# tvbgone.net
KiCad netlist of a schematic drawn in EAGLE
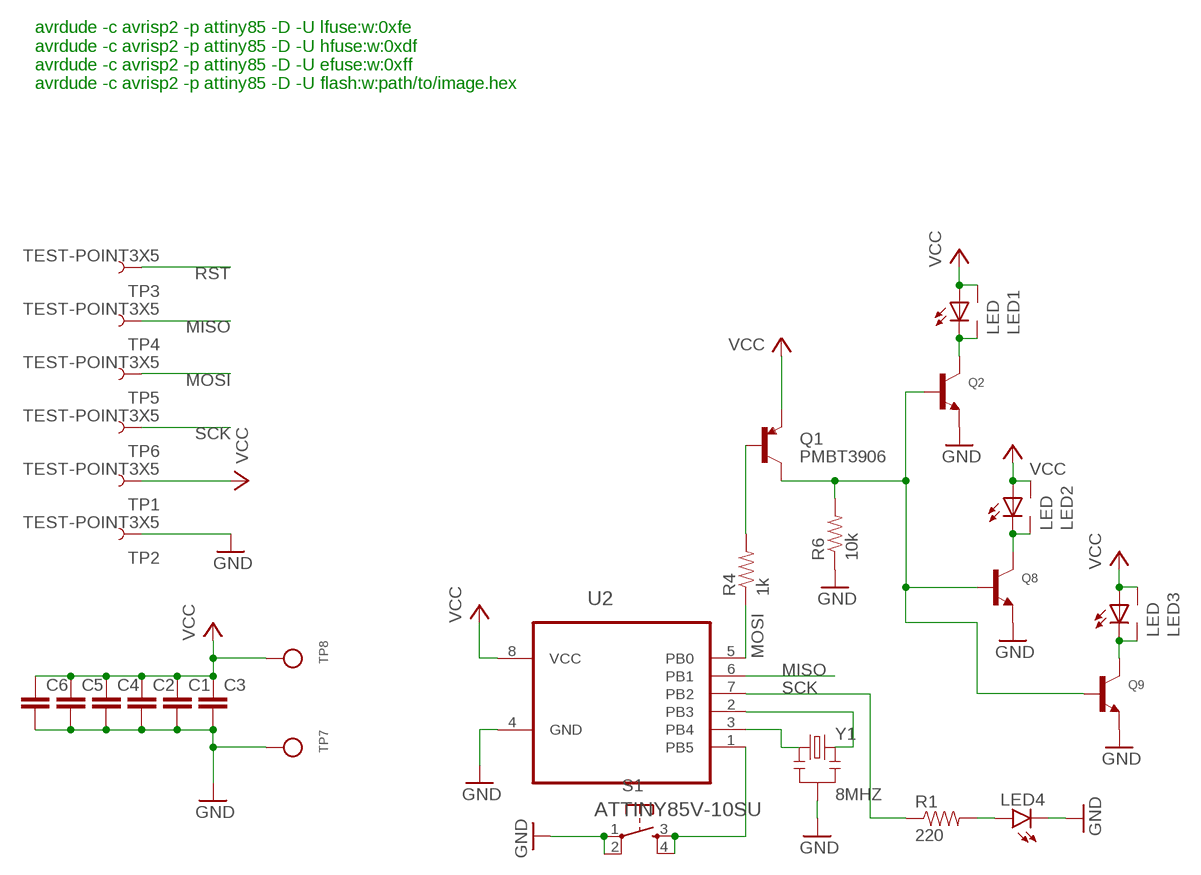
[diagram p0: schematic, sheet 1]

(export (version "E")
  (design (tool "Eeschema 10.0.6"))
  (components
    (comp (ref "C1")
      (value "CAP0603-CAP")
      (footprint "eagle-import:0603-CAP")
      (libsource (lib "eagle-import") (part "CAP0603-CAP"))
    )
    (comp (ref "C2")
      (value "CAP0603-CAP")
      (footprint "eagle-import:0603-CAP")
      (libsource (lib "eagle-import") (part "CAP0603-CAP"))
    )
    (comp (ref "C3")
      (value "CAP0603-CAP")
      (footprint "eagle-import:0603-CAP")
      (libsource (lib "eagle-import") (part "CAP0603-CAP"))
    )
    (comp (ref "C4")
      (value "CAP0603-CAP")
      (footprint "eagle-import:0603-CAP")
      (libsource (lib "eagle-import") (part "CAP0603-CAP"))
    )
    (comp (ref "C5")
      (value "CAP0603-CAP")
      (footprint "eagle-import:0603-CAP")
      (libsource (lib "eagle-import") (part "CAP0603-CAP"))
    )
    (comp (ref "C6")
      (value "CAP0603-CAP")
      (footprint "eagle-import:0603-CAP")
      (libsource (lib "eagle-import") (part "CAP0603-CAP"))
    )
    (comp (ref "LED1")
      (value "LED")
      (footprint "eagle-import:5MM-SIDE")
      (libsource (lib "eagle-import") (part "LED"))
    )
    (comp (ref "LED2")
      (value "LED")
      (footprint "eagle-import:5MM-SIDE")
      (libsource (lib "eagle-import") (part "LED"))
    )
    (comp (ref "LED3")
      (value "LED")
      (footprint "eagle-import:5MM-SIDE")
      (libsource (lib "eagle-import") (part "LED"))
    )
    (comp (ref "LED4")
      (value "LED0603")
      (footprint "eagle-import:LED-0603")
      (libsource (lib "eagle-import") (part "LED0603"))
    )
    (comp (ref "Q1")
      (value "PMBT3906")
      (footprint "eagle-import:SOT23-3")
      (libsource (lib "eagle-import") (part "TRANSISTOR_PNPPMBT3906"))
    )
    (comp (ref "Q2")
      (value "TRANSISTOR_NPN")
      (footprint "eagle-import:SOT-23-R")
      (libsource (lib "eagle-import") (part "TRANSISTOR_NPN"))
    )
    (comp (ref "Q8")
      (value "TRANSISTOR_NPN")
      (footprint "eagle-import:SOT-23-R")
      (libsource (lib "eagle-import") (part "TRANSISTOR_NPN"))
    )
    (comp (ref "Q9")
      (value "TRANSISTOR_NPN")
      (footprint "eagle-import:SOT-23-R")
      (libsource (lib "eagle-import") (part "TRANSISTOR_NPN"))
    )
    (comp (ref "R1")
      (value "220")
      (footprint "eagle-import:0603-RES")
      (libsource (lib "eagle-import") (part "RESISTOR0603"))
    )
    (comp (ref "R4")
      (value "1k")
      (footprint "eagle-import:0603-RES")
      (libsource (lib "eagle-import") (part "RESISTOR0603"))
    )
    (comp (ref "R6")
      (value "10k")
      (footprint "eagle-import:0603-RES")
      (libsource (lib "eagle-import") (part "RESISTOR0603"))
    )
    (comp (ref "S1")
      (value "TAC_SWITCHSMD")
      (footprint "eagle-import:TACTILE-SWITCH-SMD")
      (libsource (lib "eagle-import") (part "TAC_SWITCHSMD"))
    )
    (comp (ref "TP1")
      (value "TEST-POINT3X5")
      (footprint "eagle-import:PAD.03X.05")
      (libsource (lib "eagle-import") (part "TEST-POINT3X5"))
    )
    (comp (ref "TP2")
      (value "TEST-POINT3X5")
      (footprint "eagle-import:PAD.03X.05")
      (libsource (lib "eagle-import") (part "TEST-POINT3X5"))
    )
    (comp (ref "TP3")
      (value "TEST-POINT3X5")
      (footprint "eagle-import:PAD.03X.05")
      (libsource (lib "eagle-import") (part "TEST-POINT3X5"))
    )
    (comp (ref "TP4")
      (value "TEST-POINT3X5")
      (footprint "eagle-import:PAD.03X.05")
      (libsource (lib "eagle-import") (part "TEST-POINT3X5"))
    )
    (comp (ref "TP5")
      (value "TEST-POINT3X5")
      (footprint "eagle-import:PAD.03X.05")
      (libsource (lib "eagle-import") (part "TEST-POINT3X5"))
    )
    (comp (ref "TP6")
      (value "TEST-POINT3X5")
      (footprint "eagle-import:PAD.03X.05")
      (libsource (lib "eagle-import") (part "TEST-POINT3X5"))
    )
    (comp (ref "TP7")
      (value "TESTPOINTPAD")
      (footprint "eagle-import:TESTPOINT_PAD_2MM")
      (libsource (lib "eagle-import") (part "TESTPOINTPAD"))
    )
    (comp (ref "TP8")
      (value "TESTPOINTPAD")
      (footprint "eagle-import:TESTPOINT_PAD_2MM")
      (libsource (lib "eagle-import") (part "TESTPOINTPAD"))
    )
    (comp (ref "U2")
      (value "ATTINY85V-10SU")
      (footprint "eagle-import:SOIC127P798X216-8N")
      (libsource (lib "eagle-import") (part "ATTINY85V-10SU"))
    )
    (comp (ref "Y1")
      (value "8MHZ")
      (footprint "eagle-import:RESONATOR-SMD")
      (libsource (lib "eagle-import") (part "RESONATOR8MHZ"))
    )
  )
  (nets
    (net (code "1") (name "/MISO") (class "Default")
      (node (ref "TP4") (pin "P$1") (pinfunction "1_P$1") (pintype "bidirectional"))
      (node (ref "U2") (pin "6") (pinfunction "PB1_6") (pintype "bidirectional"))
    )
    (net (code "2") (name "/MOSI") (class "Default")
      (node (ref "R4") (pin "1") (pinfunction "1_1") (pintype "passive"))
      (node (ref "TP5") (pin "P$1") (pinfunction "1_P$1") (pintype "bidirectional"))
      (node (ref "U2") (pin "5") (pinfunction "PB0_5") (pintype "bidirectional"))
    )
    (net (code "3") (name "/RST") (class "Default")
      (node (ref "S1") (pin "3") (pinfunction "3_3") (pintype "passive"))
      (node (ref "S1") (pin "4") (pinfunction "4_4") (pintype "passive"))
      (node (ref "TP3") (pin "P$1") (pinfunction "1_P$1") (pintype "bidirectional"))
      (node (ref "U2") (pin "1") (pinfunction "PB5_1") (pintype "bidirectional"))
    )
    (net (code "4") (name "/SCK") (class "Default")
      (node (ref "R1") (pin "1") (pinfunction "1_1") (pintype "passive"))
      (node (ref "TP6") (pin "P$1") (pinfunction "1_P$1") (pintype "bidirectional"))
      (node (ref "U2") (pin "7") (pinfunction "PB2_7") (pintype "bidirectional"))
    )
    (net (code "5") (name "GND") (class "Default")
      (node (ref "C1") (pin "2") (pinfunction "2_2") (pintype "passive"))
      (node (ref "C2") (pin "2") (pinfunction "2_2") (pintype "passive"))
      (node (ref "C3") (pin "2") (pinfunction "2_2") (pintype "passive"))
      (node (ref "C4") (pin "2") (pinfunction "2_2") (pintype "passive"))
      (node (ref "C5") (pin "2") (pinfunction "2_2") (pintype "passive"))
      (node (ref "C6") (pin "2") (pinfunction "2_2") (pintype "passive"))
      (node (ref "LED4") (pin "C") (pinfunction "C_C") (pintype "passive"))
      (node (ref "Q2") (pin "3-EMITTER") (pinfunction "E_3-EMITTER") (pintype "passive"))
      (node (ref "Q8") (pin "3-EMITTER") (pinfunction "E_3-EMITTER") (pintype "passive"))
      (node (ref "Q9") (pin "3-EMITTER") (pinfunction "E_3-EMITTER") (pintype "passive"))
      (node (ref "R6") (pin "1") (pinfunction "1_1") (pintype "passive"))
      (node (ref "S1") (pin "1") (pinfunction "1_1") (pintype "passive"))
      (node (ref "S1") (pin "2") (pinfunction "2_2") (pintype "passive"))
      (node (ref "TP2") (pin "P$1") (pinfunction "1_P$1") (pintype "bidirectional"))
      (node (ref "TP7") (pin "P$1") (pinfunction "P$1_P$1") (pintype "bidirectional"))
      (node (ref "U2") (pin "4") (pinfunction "GND_4") (pintype "passive"))
      (node (ref "Y1") (pin "2") (pinfunction "2_2") (pintype "passive"))
    )
    (net (code "6") (name "Net-(LED1-C)") (class "Default")
      (node (ref "LED1") (pin "K") (pinfunction "C_K") (pintype "passive"))
      (node (ref "LED1") (pin "K2") (pinfunction "C1_K2") (pintype "passive"))
      (node (ref "Q2") (pin "2-COLLECTOR") (pinfunction "C_2-COLLECTOR") (pintype "passive"))
    )
    (net (code "7") (name "Net-(LED2-C)") (class "Default")
      (node (ref "LED2") (pin "K") (pinfunction "C_K") (pintype "passive"))
      (node (ref "LED2") (pin "K2") (pinfunction "C1_K2") (pintype "passive"))
      (node (ref "Q8") (pin "2-COLLECTOR") (pinfunction "C_2-COLLECTOR") (pintype "passive"))
    )
    (net (code "8") (name "Net-(LED3-C)") (class "Default")
      (node (ref "LED3") (pin "K") (pinfunction "C_K") (pintype "passive"))
      (node (ref "LED3") (pin "K2") (pinfunction "C1_K2") (pintype "passive"))
      (node (ref "Q9") (pin "2-COLLECTOR") (pinfunction "C_2-COLLECTOR") (pintype "passive"))
    )
    (net (code "9") (name "Net-(LED4-PadA)") (class "Default")
      (node (ref "LED4") (pin "A") (pinfunction "A_A") (pintype "passive"))
      (node (ref "R1") (pin "2") (pinfunction "2_2") (pintype "passive"))
    )
    (net (code "10") (name "Net-(Q1-B)") (class "Default")
      (node (ref "Q1") (pin "1") (pinfunction "B_1") (pintype "passive"))
      (node (ref "R4") (pin "2") (pinfunction "2_2") (pintype "passive"))
    )
    (net (code "11") (name "Net-(Q1-C)") (class "Default")
      (node (ref "Q1") (pin "3") (pinfunction "C_3") (pintype "passive"))
      (node (ref "Q2") (pin "1-BASE") (pinfunction "B_1-BASE") (pintype "passive"))
      (node (ref "Q8") (pin "1-BASE") (pinfunction "B_1-BASE") (pintype "passive"))
      (node (ref "Q9") (pin "1-BASE") (pinfunction "B_1-BASE") (pintype "passive"))
      (node (ref "R6") (pin "2") (pinfunction "2_2") (pintype "passive"))
    )
    (net (code "12") (name "Net-(U2-PB3)") (class "Default")
      (node (ref "U2") (pin "2") (pinfunction "PB3_2") (pintype "bidirectional"))
      (node (ref "Y1") (pin "3") (pinfunction "3_3") (pintype "passive"))
    )
    (net (code "13") (name "Net-(U2-PB4)") (class "Default")
      (node (ref "U2") (pin "3") (pinfunction "PB4_3") (pintype "bidirectional"))
      (node (ref "Y1") (pin "1") (pinfunction "1_1") (pintype "passive"))
    )
    (net (code "14") (name "VCC") (class "Default")
      (node (ref "C1") (pin "1") (pinfunction "1_1") (pintype "passive"))
      (node (ref "C2") (pin "1") (pinfunction "1_1") (pintype "passive"))
      (node (ref "C3") (pin "1") (pinfunction "1_1") (pintype "passive"))
      (node (ref "C4") (pin "1") (pinfunction "1_1") (pintype "passive"))
      (node (ref "C5") (pin "1") (pinfunction "1_1") (pintype "passive"))
      (node (ref "C6") (pin "1") (pinfunction "1_1") (pintype "passive"))
      (node (ref "LED1") (pin "A") (pinfunction "A_A") (pintype "passive"))
      (node (ref "LED1") (pin "A2") (pinfunction "A1_A2") (pintype "passive"))
      (node (ref "LED2") (pin "A") (pinfunction "A_A") (pintype "passive"))
      (node (ref "LED2") (pin "A2") (pinfunction "A1_A2") (pintype "passive"))
      (node (ref "LED3") (pin "A") (pinfunction "A_A") (pintype "passive"))
      (node (ref "LED3") (pin "A2") (pinfunction "A1_A2") (pintype "passive"))
      (node (ref "Q1") (pin "2") (pinfunction "E_2") (pintype "passive"))
      (node (ref "TP1") (pin "P$1") (pinfunction "1_P$1") (pintype "bidirectional"))
      (node (ref "TP8") (pin "P$1") (pinfunction "P$1_P$1") (pintype "bidirectional"))
      (node (ref "U2") (pin "8") (pinfunction "VCC_8") (pintype "power_in"))
    )
  )
)
